# SparkFun_XBee3_Cat1_Smart_Modem_USB-C.net
KiCad netlist of a schematic drawn in EAGLE
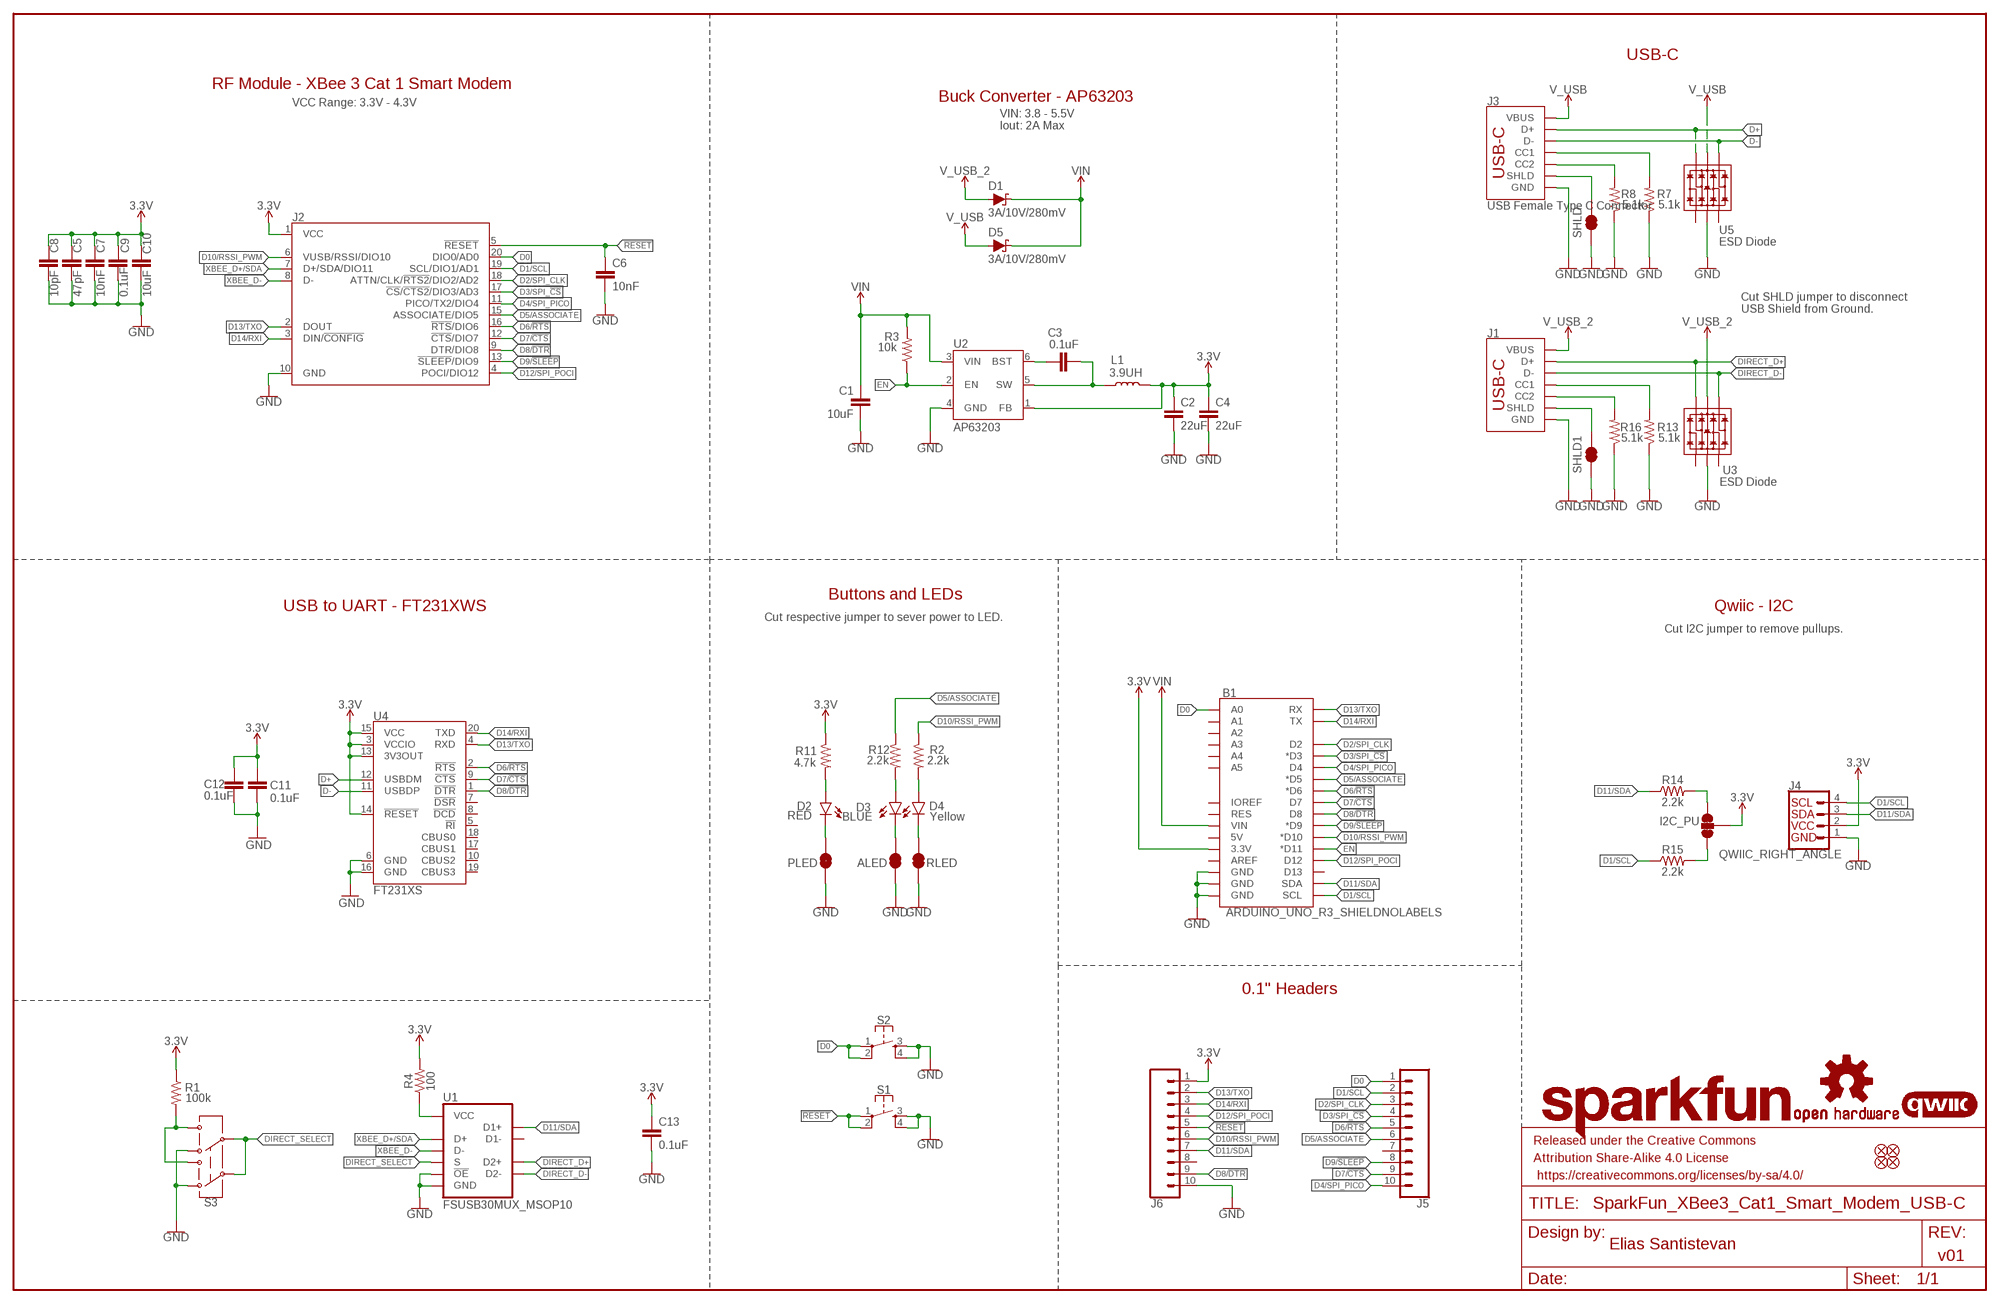
[diagram p0: schematic, sheet 1]

(export (version "E")
  (design (tool "Eeschema 10.0.6"))
  (components
    (comp (ref "ALED")
      (value "JUMPER-SMT_2_NC_TRACE_SILK")
      (footprint "eagle-import:SMT-JUMPER_2_NC_TRACE_SILK")
      (libsource (lib "eagle-import") (part "JUMPER-SMT_2_NC_TRACE_SILK"))
    )
    (comp (ref "B1")
      (value "ARDUINO_UNO_R3_SHIELDNOLABELS")
      (footprint "eagle-import:UNO_R3_SHIELD_NOLABELS")
      (libsource (lib "eagle-import") (part "ARDUINO_UNO_R3_SHIELDNOLABELS"))
    )
    (comp (ref "C1")
      (value "10uF")
      (footprint "eagle-import:1210")
      (libsource (lib "eagle-import") (part "10UF-1210-50V-20%"))
    )
    (comp (ref "C2")
      (value "22uF")
      (footprint "eagle-import:0603")
      (libsource (lib "eagle-import") (part "22UF-0603-6.3V-20%"))
    )
    (comp (ref "C3")
      (value "0.1uF")
      (footprint "eagle-import:0603")
      (libsource (lib "eagle-import") (part "0.1UF-0603-25V-5%"))
    )
    (comp (ref "C4")
      (value "22uF")
      (footprint "eagle-import:0603")
      (libsource (lib "eagle-import") (part "22UF-0603-6.3V-20%"))
    )
    (comp (ref "C5")
      (value "47pF")
      (footprint "eagle-import:0603")
      (libsource (lib "eagle-import") (part "47PF-0603-50V-5%"))
    )
    (comp (ref "C6")
      (value "10nF")
      (footprint "eagle-import:0603")
      (libsource (lib "eagle-import") (part "10NF-0603-50V-10%"))
    )
    (comp (ref "C7")
      (value "10nF")
      (footprint "eagle-import:0603")
      (libsource (lib "eagle-import") (part "10NF-0603-50V-10%"))
    )
    (comp (ref "C8")
      (value "10pF")
      (footprint "eagle-import:0603")
      (libsource (lib "eagle-import") (part "10PF-0603-50V-5%"))
    )
    (comp (ref "C9")
      (value "0.1uF")
      (footprint "eagle-import:0603")
      (libsource (lib "eagle-import") (part "0.1UF-0603-25V-(+80/-20%)"))
    )
    (comp (ref "C10")
      (value "10uF")
      (footprint "eagle-import:0603")
      (libsource (lib "eagle-import") (part "10UF-0603-6.3V-20%"))
    )
    (comp (ref "C11")
      (value "0.1uF")
      (footprint "eagle-import:0603")
      (libsource (lib "eagle-import") (part "0.1UF-0603-25V-(+80/-20%)"))
    )
    (comp (ref "C12")
      (value "0.1uF")
      (footprint "eagle-import:0603")
      (libsource (lib "eagle-import") (part "0.1UF-0603-25V-(+80/-20%)"))
    )
    (comp (ref "C13")
      (value "0.1uF")
      (footprint "eagle-import:0603")
      (libsource (lib "eagle-import") (part "0.1UF-0603-25V-(+80/-20%)"))
    )
    (comp (ref "D1")
      (value "3A/10V/280mV")
      (footprint "eagle-import:SOD-323")
      (libsource (lib "eagle-import") (part "DIODE-SCHOTTKY-BAT60A"))
    )
    (comp (ref "D2")
      (value "RED")
      (footprint "eagle-import:LED-0603")
      (libsource (lib "eagle-import") (part "LED-RED_0603-KB"))
    )
    (comp (ref "D3")
      (value "BLUE")
      (footprint "eagle-import:LED-0603")
      (libsource (lib "eagle-import") (part "LED-BLUE0603"))
    )
    (comp (ref "D4")
      (value "Yellow")
      (footprint "eagle-import:LED-0603")
      (libsource (lib "eagle-import") (part "LED-YELLOW0603"))
    )
    (comp (ref "D5")
      (value "3A/10V/280mV")
      (footprint "eagle-import:SOD-323")
      (libsource (lib "eagle-import") (part "DIODE-SCHOTTKY-BAT60A"))
    )
    (comp (ref "FD1")
      (value "FIDUCIAL1X2")
      (footprint "eagle-import:FIDUCIAL-1X2")
      (libsource (lib "eagle-import") (part "FIDUCIAL1X2"))
    )
    (comp (ref "FD2")
      (value "FIDUCIAL1X2")
      (footprint "eagle-import:FIDUCIAL-1X2")
      (libsource (lib "eagle-import") (part "FIDUCIAL1X2"))
    )
    (comp (ref "FD3")
      (value "FIDUCIAL1X2")
      (footprint "eagle-import:FIDUCIAL-1X2")
      (libsource (lib "eagle-import") (part "FIDUCIAL1X2"))
    )
    (comp (ref "FD4")
      (value "FIDUCIAL1X2")
      (footprint "eagle-import:FIDUCIAL-1X2")
      (libsource (lib "eagle-import") (part "FIDUCIAL1X2"))
    )
    (comp (ref "FRAME1")
      (value "FRAME-LEDGER")
      (footprint "eagle-import:CREATIVE_COMMONS")
      (libsource (lib "eagle-import") (part "FRAME-LEDGER"))
    )
    (comp (ref "I2C_PU")
      (value "JUMPER-SMT_3_2-NC_TRACE_SILK")
      (footprint "eagle-import:SMT-JUMPER_3_2-NC_TRACE_SILK")
      (libsource (lib "eagle-import") (part "JUMPER-SMT_3_2-NC_TRACE_SILK"))
    )
    (comp (ref "J1")
      (value "USB Female Type C Connector")
      (footprint "eagle-import:USB-C-16P-4LAYER-ISOLATED")
      (libsource (lib "eagle-import") (part "USB_C_4-LAYER-ISOLATED"))
    )
    (comp (ref "J2")
      (value "XBEE_UPDATEXBEE_SMD_SILK")
      (footprint "eagle-import:XBEE3-SMD_SILK")
      (libsource (lib "eagle-import") (part "XBEE_UPDATEXBEE_SMD_SILK"))
    )
    (comp (ref "J3")
      (value "USB Female Type C Connector")
      (footprint "eagle-import:USB-C-16P-4LAYER-ISOLATED")
      (libsource (lib "eagle-import") (part "USB_C_4-LAYER-ISOLATED"))
    )
    (comp (ref "J4")
      (value "QWIIC_RIGHT_ANGLE")
      (footprint "eagle-import:JST04_1MM_RA")
      (libsource (lib "eagle-import") (part "QWIIC_CONNECTORJS-1MM"))
    )
    (comp (ref "J5")
      (value "CONN_10NO_SILK_PTH_FEMALE")
      (footprint "eagle-import:1X10_NO_SILK")
      (libsource (lib "eagle-import") (part "CONN_10NO_SILK_PTH_FEMALE"))
    )
    (comp (ref "J6")
      (value "CONN_10NO_SILK_PTH_FEMALE")
      (footprint "eagle-import:1X10_NO_SILK")
      (libsource (lib "eagle-import") (part "CONN_10NO_SILK_PTH_FEMALE"))
    )
    (comp (ref "L1")
      (value "3.9UH")
      (footprint "eagle-import:INDUCTOR_3.9UH")
      (libsource (lib "eagle-import") (part "3.9UH"))
    )
    (comp (ref "LOGO1")
      (value "SFE_LOGO_NAME.1_INCH")
      (footprint "eagle-import:SFE_LOGO_NAME_.1")
      (libsource (lib "eagle-import") (part "SFE_LOGO_NAME.1_INCH"))
    )
    (comp (ref "LOGO2")
      (value "OSHW-LOGOS")
      (footprint "eagle-import:OSHW-LOGO-S")
      (libsource (lib "eagle-import") (part "OSHW-LOGOS"))
    )
    (comp (ref "LOGO3")
      (value "QWIIC_LOGO_3MM")
      (footprint "eagle-import:QWIIC_3MM")
      (libsource (lib "eagle-import") (part "QWIIC_LOGO_3MM"))
    )
    (comp (ref "PLED")
      (value "JUMPER-SMT_2_NC_TRACE_SILK")
      (footprint "eagle-import:SMT-JUMPER_2_NC_TRACE_SILK")
      (libsource (lib "eagle-import") (part "JUMPER-SMT_2_NC_TRACE_SILK"))
    )
    (comp (ref "R1")
      (value "100k")
      (footprint "eagle-import:0603")
      (libsource (lib "eagle-import") (part "100KOHM-0603-1/10W-1%"))
    )
    (comp (ref "R2")
      (value "2.2k")
      (footprint "eagle-import:0603")
      (libsource (lib "eagle-import") (part "2.2KOHM-0603-1/10W-1%"))
    )
    (comp (ref "R3")
      (value "10k")
      (footprint "eagle-import:0603")
      (libsource (lib "eagle-import") (part "10KOHM-0603-1/10W-1%"))
    )
    (comp (ref "R4")
      (value "100")
      (footprint "eagle-import:0603")
      (libsource (lib "eagle-import") (part "100OHM-0603-1/10W-1%"))
    )
    (comp (ref "R7")
      (value "5.1k")
      (footprint "eagle-import:0603")
      (libsource (lib "eagle-import") (part "5.1KOHM5.1KOHM-0603-1/10W-1%"))
    )
    (comp (ref "R8")
      (value "5.1k")
      (footprint "eagle-import:0603")
      (libsource (lib "eagle-import") (part "5.1KOHM5.1KOHM-0603-1/10W-1%"))
    )
    (comp (ref "R11")
      (value "4.7k")
      (footprint "eagle-import:0603")
      (libsource (lib "eagle-import") (part "4.7KOHM-0603-1/10W-1%"))
    )
    (comp (ref "R12")
      (value "2.2k")
      (footprint "eagle-import:0603")
      (libsource (lib "eagle-import") (part "2.2KOHM-0603-1/10W-1%"))
    )
    (comp (ref "R13")
      (value "5.1k")
      (footprint "eagle-import:0603")
      (libsource (lib "eagle-import") (part "5.1KOHM5.1KOHM-0603-1/10W-1%"))
    )
    (comp (ref "R14")
      (value "2.2k")
      (footprint "eagle-import:0603")
      (libsource (lib "eagle-import") (part "2.2KOHM-0603-1/10W-1%"))
    )
    (comp (ref "R15")
      (value "2.2k")
      (footprint "eagle-import:0603")
      (libsource (lib "eagle-import") (part "2.2KOHM-0603-1/10W-1%"))
    )
    (comp (ref "R16")
      (value "5.1k")
      (footprint "eagle-import:0603")
      (libsource (lib "eagle-import") (part "5.1KOHM5.1KOHM-0603-1/10W-1%"))
    )
    (comp (ref "RLED")
      (value "JUMPER-SMT_2_NC_TRACE_SILK")
      (footprint "eagle-import:SMT-JUMPER_2_NC_TRACE_SILK")
      (libsource (lib "eagle-import") (part "JUMPER-SMT_2_NC_TRACE_SILK"))
    )
    (comp (ref "S1")
      (value "MOMENTARY-SWITCH-SPST-2-SMD-5.2MM-TALL")
      (footprint "eagle-import:TACTILE_SWITCH_SMD_5.2MM")
      (libsource (lib "eagle-import") (part "MOMENTARY-SWITCH-SPST-2-SMD-5.2MM-TALL"))
    )
    (comp (ref "S2")
      (value "MOMENTARY-SWITCH-SPST-2-SMD-5.2MM-TALL")
      (footprint "eagle-import:TACTILE_SWITCH_SMD_5.2MM")
      (libsource (lib "eagle-import") (part "MOMENTARY-SWITCH-SPST-2-SMD-5.2MM-TALL"))
    )
    (comp (ref "S3")
      (value "SWITCH-DPDT-SMD-AYZ0202")
      (footprint "eagle-import:SWITCH_DPDT_SMD_AYZ0202")
      (libsource (lib "eagle-import") (part "SWITCH-DPDT-SMD-AYZ0202"))
    )
    (comp (ref "SHLD")
      (value "JUMPER-SMT_2_NC_TRACE_SILK")
      (footprint "eagle-import:SMT-JUMPER_2_NC_TRACE_SILK")
      (libsource (lib "eagle-import") (part "JUMPER-SMT_2_NC_TRACE_SILK"))
    )
    (comp (ref "SHLD1")
      (value "JUMPER-SMT_2_NC_TRACE_SILK")
      (footprint "eagle-import:SMT-JUMPER_2_NC_TRACE_SILK")
      (libsource (lib "eagle-import") (part "JUMPER-SMT_2_NC_TRACE_SILK"))
    )
    (comp (ref "U1")
      (value "FSUSB30MUX_MSOP10")
      (footprint "eagle-import:MSOP10")
      (libsource (lib "eagle-import") (part "FSUSB30MUX_MSOP10"))
    )
    (comp (ref "U2")
      (value "AP63203")
      (footprint "eagle-import:SOT23-6")
      (libsource (lib "eagle-import") (part "AP63203"))
    )
    (comp (ref "U3")
      (value "ESD Diode")
      (footprint "eagle-import:SOT-23-6")
      (libsource (lib "eagle-import") (part "TVS_DIODE_ARRAY_DT1042-04SO-7"))
    )
    (comp (ref "U4")
      (value "FT231XS")
      (footprint "eagle-import:SSOP20_L")
      (libsource (lib "eagle-import") (part "FT231XS"))
    )
    (comp (ref "U5")
      (value "ESD Diode")
      (footprint "eagle-import:SOT-23-6")
      (libsource (lib "eagle-import") (part "TVS_DIODE_ARRAY_DT1042-04SO-7"))
    )
  )
  (nets
    (net (code "1") (name "/D3{slash}SPI_~{CS}") (class "Default")
      (node (ref "B1") (pin "D3") (pinfunction "*D3_D3") (pintype "bidirectional"))
      (node (ref "J2") (pin "17") (pinfunction "~{CS}/~{CTS2}/DIO3/AD3_17") (pintype "bidirectional"))
      (node (ref "J5") (pin "4") (pinfunction "4_4") (pintype "passive"))
    )
    (net (code "2") (name "/D6{slash}~{RTS}") (class "Default")
      (node (ref "B1") (pin "D6") (pinfunction "*D6_D6") (pintype "bidirectional"))
      (node (ref "J2") (pin "16") (pinfunction "~{RTS}/DIO6_16") (pintype "input"))
      (node (ref "J5") (pin "5") (pinfunction "5_5") (pintype "passive"))
      (node (ref "U4") (pin "2") (pinfunction "~{RTS}_2") (pintype "bidirectional"))
    )
    (net (code "3") (name "/D7{slash}~{CTS}") (class "Default")
      (node (ref "B1") (pin "D7") (pinfunction "D7_D7") (pintype "bidirectional"))
      (node (ref "J2") (pin "12") (pinfunction "~{CTS}/DIO7_12") (pintype "output"))
      (node (ref "J5") (pin "9") (pinfunction "9_9") (pintype "passive"))
      (node (ref "U4") (pin "9") (pinfunction "~{CTS}_9") (pintype "bidirectional"))
    )
    (net (code "4") (name "/D8{slash}~{DTR}") (class "Default")
      (node (ref "B1") (pin "D8") (pinfunction "D8_D8") (pintype "bidirectional"))
      (node (ref "J2") (pin "9") (pinfunction "DTR/DIO8_9") (pintype "bidirectional"))
      (node (ref "J6") (pin "9") (pinfunction "9_9") (pintype "passive"))
      (node (ref "U4") (pin "1") (pinfunction "~{DTR}_1") (pintype "bidirectional"))
    )
    (net (code "5") (name "/D9{slash}~{SLEEP}") (class "Default")
      (node (ref "B1") (pin "D9") (pinfunction "*D9_D9") (pintype "bidirectional"))
      (node (ref "J2") (pin "13") (pinfunction "~{SLEEP}/DIO9_13") (pintype "bidirectional"))
      (node (ref "J5") (pin "8") (pinfunction "8_8") (pintype "passive"))
    )
    (net (code "6") (name "/~{RESET}") (class "Default")
      (node (ref "C6") (pin "1") (pinfunction "1_1") (pintype "passive"))
      (node (ref "J2") (pin "5") (pinfunction "~{RESET}_5") (pintype "input"))
      (node (ref "J6") (pin "5") (pinfunction "5_5") (pintype "passive"))
      (node (ref "S1") (pin "1") (pinfunction "1_1") (pintype "passive"))
      (node (ref "S1") (pin "2") (pinfunction "2_2") (pintype "passive"))
    )
    (net (code "7") (name "3.3V") (class "Default")
      (node (ref "B1") (pin "3.3V") (pinfunction "3.3V_3.3V") (pintype "bidirectional"))
      (node (ref "C10") (pin "1") (pinfunction "1_1") (pintype "passive"))
      (node (ref "C11") (pin "1") (pinfunction "1_1") (pintype "passive"))
      (node (ref "C12") (pin "1") (pinfunction "1_1") (pintype "passive"))
      (node (ref "C13") (pin "1") (pinfunction "1_1") (pintype "passive"))
      (node (ref "C2") (pin "1") (pinfunction "1_1") (pintype "passive"))
      (node (ref "C4") (pin "1") (pinfunction "1_1") (pintype "passive"))
      (node (ref "C5") (pin "1") (pinfunction "1_1") (pintype "passive"))
      (node (ref "C7") (pin "1") (pinfunction "1_1") (pintype "passive"))
      (node (ref "C8") (pin "1") (pinfunction "1_1") (pintype "passive"))
      (node (ref "C9") (pin "1") (pinfunction "1_1") (pintype "passive"))
      (node (ref "I2C_PU") (pin "2") (pinfunction "2_2") (pintype "passive"))
      (node (ref "J2") (pin "1") (pinfunction "VCC_1") (pintype "power_in"))
      (node (ref "J4") (pin "2") (pinfunction "2_2") (pintype "power_in"))
      (node (ref "J6") (pin "1") (pinfunction "1_1") (pintype "passive"))
      (node (ref "L1") (pin "P$2") (pinfunction "2_P$2") (pintype "passive"))
      (node (ref "R1") (pin "1") (pinfunction "1_1") (pintype "passive"))
      (node (ref "R11") (pin "1") (pinfunction "1_1") (pintype "passive"))
      (node (ref "R4") (pin "2") (pinfunction "2_2") (pintype "passive"))
      (node (ref "U2") (pin "1") (pinfunction "FB_1") (pintype "bidirectional"))
      (node (ref "U4") (pin "13") (pinfunction "3V3OUT_13") (pintype "bidirectional"))
      (node (ref "U4") (pin "14") (pinfunction "~{RESET}_14") (pintype "bidirectional"))
      (node (ref "U4") (pin "15") (pinfunction "VCC_15") (pintype "bidirectional"))
      (node (ref "U4") (pin "3") (pinfunction "VCCIO_3") (pintype "bidirectional"))
    )
    (net (code "8") (name "D+") (class "Default")
      (node (ref "J3") (pin "A6") (pinfunction "D+_A6") (pintype "bidirectional"))
      (node (ref "J3") (pin "B6") (pinfunction "D+_B6") (pintype "bidirectional"))
      (node (ref "U4") (pin "12") (pinfunction "USBDM_12") (pintype "bidirectional"))
      (node (ref "U5") (pin "6") (pinfunction "IO4_6") (pintype "bidirectional"))
    )
    (net (code "9") (name "D-") (class "Default")
      (node (ref "J3") (pin "A7") (pinfunction "D-_A7") (pintype "bidirectional"))
      (node (ref "J3") (pin "B7") (pinfunction "D-_B7") (pintype "bidirectional"))
      (node (ref "U4") (pin "11") (pinfunction "USBDP_11") (pintype "bidirectional"))
      (node (ref "U5") (pin "4") (pinfunction "IO3_4") (pintype "bidirectional"))
    )
    (net (code "10") (name "D0") (class "Default")
      (node (ref "B1") (pin "A0") (pinfunction "A0_A0") (pintype "bidirectional"))
      (node (ref "J2") (pin "20") (pinfunction "DIO0/AD0_20") (pintype "bidirectional"))
      (node (ref "J5") (pin "1") (pinfunction "1_1") (pintype "passive"))
      (node (ref "S2") (pin "1") (pinfunction "1_1") (pintype "passive"))
      (node (ref "S2") (pin "2") (pinfunction "2_2") (pintype "passive"))
    )
    (net (code "11") (name "D1{slash}SCL") (class "Default")
      (node (ref "B1") (pin "SCL") (pinfunction "SCL_SCL") (pintype "bidirectional"))
      (node (ref "J2") (pin "19") (pinfunction "SCL/DIO1/AD1_19") (pintype "bidirectional"))
      (node (ref "J4") (pin "4") (pinfunction "4_4") (pintype "passive"))
      (node (ref "J5") (pin "2") (pinfunction "2_2") (pintype "passive"))
      (node (ref "R15") (pin "1") (pinfunction "1_1") (pintype "passive"))
    )
    (net (code "12") (name "D2{slash}SPI_CLK") (class "Default")
      (node (ref "B1") (pin "D2") (pinfunction "D2_D2") (pintype "bidirectional"))
      (node (ref "J2") (pin "18") (pinfunction "ATTN/CLK/~{RTS2}/DIO2/AD2_18") (pintype "bidirectional"))
      (node (ref "J5") (pin "3") (pinfunction "3_3") (pintype "passive"))
    )
    (net (code "13") (name "D4{slash}SPI_PICO") (class "Default")
      (node (ref "B1") (pin "D4") (pinfunction "D4_D4") (pintype "bidirectional"))
      (node (ref "J2") (pin "11") (pinfunction "PICO/TX2/DIO4_11") (pintype "bidirectional"))
      (node (ref "J5") (pin "10") (pinfunction "10_10") (pintype "passive"))
    )
    (net (code "14") (name "D5{slash}ASSOCIATE") (class "Default")
      (node (ref "B1") (pin "D5") (pinfunction "*D5_D5") (pintype "bidirectional"))
      (node (ref "J2") (pin "15") (pinfunction "ASSOCIATE/DIO5_15") (pintype "bidirectional"))
      (node (ref "J5") (pin "6") (pinfunction "6_6") (pintype "passive"))
      (node (ref "R12") (pin "1") (pinfunction "1_1") (pintype "passive"))
    )
    (net (code "15") (name "D10{slash}RSSI_PWM") (class "Default")
      (node (ref "B1") (pin "D10") (pinfunction "*D10_D10") (pintype "bidirectional"))
      (node (ref "J2") (pin "6") (pinfunction "VUSB/RSSI/DIO10_6") (pintype "bidirectional"))
      (node (ref "J6") (pin "6") (pinfunction "6_6") (pintype "passive"))
      (node (ref "R2") (pin "1") (pinfunction "1_1") (pintype "passive"))
    )
    (net (code "16") (name "D11{slash}SDA") (class "Default")
      (node (ref "B1") (pin "SDA") (pinfunction "SDA_SDA") (pintype "bidirectional"))
      (node (ref "J4") (pin "3") (pinfunction "3_3") (pintype "passive"))
      (node (ref "J6") (pin "7") (pinfunction "7_7") (pintype "passive"))
      (node (ref "R14") (pin "1") (pinfunction "1_1") (pintype "passive"))
      (node (ref "U1") (pin "2") (pinfunction "D1+_2") (pintype "bidirectional"))
    )
    (net (code "17") (name "D12{slash}SPI_POCI") (class "Default")
      (node (ref "B1") (pin "D12") (pinfunction "D12_D12") (pintype "bidirectional"))
      (node (ref "J2") (pin "4") (pinfunction "POCI/DIO12_4") (pintype "bidirectional"))
      (node (ref "J6") (pin "4") (pinfunction "4_4") (pintype "passive"))
    )
    (net (code "18") (name "D13{slash}TXO") (class "Default")
      (node (ref "B1") (pin "RX") (pinfunction "RX_RX") (pintype "bidirectional"))
      (node (ref "J2") (pin "2") (pinfunction "DOUT_2") (pintype "output"))
      (node (ref "J6") (pin "2") (pinfunction "2_2") (pintype "passive"))
      (node (ref "U4") (pin "4") (pinfunction "RXD_4") (pintype "bidirectional"))
    )
    (net (code "19") (name "D14{slash}RXI") (class "Default")
      (node (ref "B1") (pin "TX") (pinfunction "TX_TX") (pintype "bidirectional"))
      (node (ref "J2") (pin "3") (pinfunction "DIN/~{CONFIG}_3") (pintype "input"))
      (node (ref "J6") (pin "3") (pinfunction "3_3") (pintype "passive"))
      (node (ref "U4") (pin "20") (pinfunction "TXD_20") (pintype "bidirectional"))
    )
    (net (code "20") (name "DIRECT_D+") (class "Default")
      (node (ref "J1") (pin "A6") (pinfunction "D+_A6") (pintype "bidirectional"))
      (node (ref "J1") (pin "B6") (pinfunction "D+_B6") (pintype "bidirectional"))
      (node (ref "U1") (pin "3") (pinfunction "D2+_3") (pintype "bidirectional"))
      (node (ref "U3") (pin "6") (pinfunction "IO4_6") (pintype "bidirectional"))
    )
    (net (code "21") (name "DIRECT_D-") (class "Default")
      (node (ref "J1") (pin "A7") (pinfunction "D-_A7") (pintype "bidirectional"))
      (node (ref "J1") (pin "B7") (pinfunction "D-_B7") (pintype "bidirectional"))
      (node (ref "U1") (pin "7") (pinfunction "D2-_7") (pintype "bidirectional"))
      (node (ref "U3") (pin "4") (pinfunction "IO3_4") (pintype "bidirectional"))
    )
    (net (code "22") (name "DIRECT_SELECT") (class "Default")
      (node (ref "S3") (pin "2") (pinfunction "2_2") (pintype "bidirectional"))
      (node (ref "S3") (pin "5") (pinfunction "5_5") (pintype "bidirectional"))
      (node (ref "U1") (pin "1") (pinfunction "S_1") (pintype "bidirectional"))
    )
    (net (code "23") (name "EN") (class "Default")
      (node (ref "B1") (pin "D11") (pinfunction "*D11_D11") (pintype "bidirectional"))
      (node (ref "R3") (pin "1") (pinfunction "1_1") (pintype "passive"))
      (node (ref "U2") (pin "2") (pinfunction "EN_2") (pintype "bidirectional"))
    )
    (net (code "24") (name "GND") (class "Default")
      (node (ref "ALED") (pin "1") (pinfunction "1_1") (pintype "passive"))
      (node (ref "B1") (pin "GND@0") (pinfunction "GND_GND@0") (pintype "bidirectional"))
      (node (ref "B1") (pin "GND@1") (pinfunction "GND_GND@1") (pintype "bidirectional"))
      (node (ref "B1") (pin "GND@2") (pinfunction "GND_GND@2") (pintype "bidirectional"))
      (node (ref "C1") (pin "2") (pinfunction "2_2") (pintype "passive"))
      (node (ref "C10") (pin "2") (pinfunction "2_2") (pintype "passive"))
      (node (ref "C11") (pin "2") (pinfunction "2_2") (pintype "passive"))
      (node (ref "C12") (pin "2") (pinfunction "2_2") (pintype "passive"))
      (node (ref "C13") (pin "2") (pinfunction "2_2") (pintype "passive"))
      (node (ref "C2") (pin "2") (pinfunction "2_2") (pintype "passive"))
      (node (ref "C4") (pin "2") (pinfunction "2_2") (pintype "passive"))
      (node (ref "C5") (pin "2") (pinfunction "2_2") (pintype "passive"))
      (node (ref "C6") (pin "2") (pinfunction "2_2") (pintype "passive"))
      (node (ref "C7") (pin "2") (pinfunction "2_2") (pintype "passive"))
      (node (ref "C8") (pin "2") (pinfunction "2_2") (pintype "passive"))
      (node (ref "C9") (pin "2") (pinfunction "2_2") (pintype "passive"))
      (node (ref "J1") (pin "GND") (pinfunction "GND_GND") (pintype "bidirectional"))
      (node (ref "J1") (pin "GND2") (pinfunction "GND_GND2") (pintype "bidirectional"))
      (node (ref "J2") (pin "10") (pinfunction "GND_10") (pintype "power_in"))
      (node (ref "J3") (pin "GND") (pinfunction "GND_GND") (pintype "bidirectional"))
      (node (ref "J3") (pin "GND2") (pinfunction "GND_GND2") (pintype "bidirectional"))
      (node (ref "J4") (pin "1") (pinfunction "1_1") (pintype "power_in"))
      (node (ref "J6") (pin "10") (pinfunction "10_10") (pintype "passive"))
      (node (ref "PLED") (pin "1") (pinfunction "1_1") (pintype "passive"))
      (node (ref "R13") (pin "1") (pinfunction "1_1") (pintype "passive"))
      (node (ref "R16") (pin "1") (pinfunction "1_1") (pintype "passive"))
      (node (ref "R7") (pin "1") (pinfunction "1_1") (pintype "passive"))
      (node (ref "R8") (pin "1") (pinfunction "1_1") (pintype "passive"))
      (node (ref "RLED") (pin "1") (pinfunction "1_1") (pintype "passive"))
      (node (ref "S1") (pin "3") (pinfunction "3_3") (pintype "passive"))
      (node (ref "S1") (pin "4") (pinfunction "4_4") (pintype "passive"))
      (node (ref "S2") (pin "3") (pinfunction "3_3") (pintype "passive"))
      (node (ref "S2") (pin "4") (pinfunction "4_4") (pintype "passive"))
      (node (ref "S3") (pin "3") (pinfunction "3_3") (pintype "bidirectional"))
      (node (ref "S3") (pin "6") (pinfunction "6_6") (pintype "bidirectional"))
      (node (ref "SHLD") (pin "1") (pinfunction "1_1") (pintype "passive"))
      (node (ref "SHLD1") (pin "1") (pinfunction "1_1") (pintype "passive"))
      (node (ref "U1") (pin "5") (pinfunction "GND_5") (pintype "bidirectional"))
      (node (ref "U1") (pin "9") (pinfunction "~{OE}_9") (pintype "bidirectional"))
      (node (ref "U2") (pin "4") (pinfunction "GND_4") (pintype "bidirectional"))
      (node (ref "U3") (pin "2") (pinfunction "VSS_2") (pintype "bidirectional"))
      (node (ref "U4") (pin "16") (pinfunction "GND_16") (pintype "bidirectional"))
      (node (ref "U4") (pin "6") (pinfunction "GND_6") (pintype "bidirectional"))
      (node (ref "U5") (pin "2") (pinfunction "VSS_2") (pintype "bidirectional"))
    )
    (net (code "25") (name "Net-(ALED-Pad2)") (class "Default")
      (node (ref "ALED") (pin "2") (pinfunction "2_2") (pintype "passive"))
      (node (ref "D3") (pin "C") (pinfunction "C_C") (pintype "passive"))
    )
    (net (code "26") (name "Net-(D2-PadA)") (class "Default")
      (node (ref "D2") (pin "A") (pinfunction "A_A") (pintype "passive"))
      (node (ref "R11") (pin "2") (pinfunction "2_2") (pintype "passive"))
    )
    (net (code "27") (name "Net-(D2-PadC)") (class "Default")
      (node (ref "D2") (pin "C") (pinfunction "C_C") (pintype "passive"))
      (node (ref "PLED") (pin "2") (pinfunction "2_2") (pintype "passive"))
    )
    (net (code "28") (name "Net-(D3-PadA)") (class "Default")
      (node (ref "D3") (pin "A") (pinfunction "A_A") (pintype "passive"))
      (node (ref "R12") (pin "2") (pinfunction "2_2") (pintype "passive"))
    )
    (net (code "29") (name "Net-(D4-PadA)") (class "Default")
      (node (ref "D4") (pin "A") (pinfunction "A_A") (pintype "passive"))
      (node (ref "R2") (pin "2") (pinfunction "2_2") (pintype "passive"))
    )
    (net (code "30") (name "Net-(D4-PadC)") (class "Default")
      (node (ref "D4") (pin "C") (pinfunction "C_C") (pintype "passive"))
      (node (ref "RLED") (pin "2") (pinfunction "2_2") (pintype "passive"))
    )
    (net (code "31") (name "Net-(I2C_PU-Pad1)") (class "Default")
      (node (ref "I2C_PU") (pin "1") (pinfunction "1_1") (pintype "passive"))
      (node (ref "R15") (pin "2") (pinfunction "2_2") (pintype "passive"))
    )
    (net (code "32") (name "Net-(I2C_PU-Pad3)") (class "Default")
      (node (ref "I2C_PU") (pin "3") (pinfunction "3_3") (pintype "passive"))
      (node (ref "R14") (pin "2") (pinfunction "2_2") (pintype "passive"))
    )
    (net (code "33") (name "Net-(J1-CC1)") (class "Default")
      (node (ref "J1") (pin "A5") (pinfunction "CC1_A5") (pintype "bidirectional"))
      (node (ref "R13") (pin "2") (pinfunction "2_2") (pintype "passive"))
    )
    (net (code "34") (name "Net-(J1-CC2)") (class "Default")
      (node (ref "J1") (pin "B5") (pinfunction "CC2_B5") (pintype "bidirectional"))
      (node (ref "R16") (pin "2") (pinfunction "2_2") (pintype "passive"))
    )
    (net (code "35") (name "Net-(J1-SHLD-PadSHLD1)") (class "Default")
      (node (ref "J1") (pin "SHLD1") (pinfunction "SHLD_SHLD1") (pintype "bidirectional"))
      (node (ref "J1") (pin "SHLD2") (pinfunction "SHLD_SHLD2") (pintype "bidirectional"))
      (node (ref "J1") (pin "SHLD3") (pinfunction "SHLD_SHLD3") (pintype "bidirectional"))
      (node (ref "J1") (pin "SHLD4") (pinfunction "SHLD_SHLD4") (pintype "bidirectional"))
      (node (ref "J1") (pin "SHLD5") (pinfunction "SHLD_SHLD5") (pintype "bidirectional"))
      (node (ref "J1") (pin "SHLD6") (pinfunction "SHLD_SHLD6") (pintype "bidirectional"))
      (node (ref "J1") (pin "SHLD7") (pinfunction "SHLD_SHLD7") (pintype "bidirectional"))
      (node (ref "J1") (pin "SHLD8") (pinfunction "SHLD_SHLD8") (pintype "bidirectional"))
      (node (ref "SHLD1") (pin "2") (pinfunction "2_2") (pintype "passive"))
    )
    (net (code "36") (name "Net-(J3-CC1)") (class "Default")
      (node (ref "J3") (pin "A5") (pinfunction "CC1_A5") (pintype "bidirectional"))
      (node (ref "R7") (pin "2") (pinfunction "2_2") (pintype "passive"))
    )
    (net (code "37") (name "Net-(J3-CC2)") (class "Default")
      (node (ref "J3") (pin "B5") (pinfunction "CC2_B5") (pintype "bidirectional"))
      (node (ref "R8") (pin "2") (pinfunction "2_2") (pintype "passive"))
    )
    (net (code "38") (name "Net-(J3-SHLD-PadSHLD1)") (class "Default")
      (node (ref "J3") (pin "SHLD1") (pinfunction "SHLD_SHLD1") (pintype "bidirectional"))
      (node (ref "J3") (pin "SHLD2") (pinfunction "SHLD_SHLD2") (pintype "bidirectional"))
      (node (ref "J3") (pin "SHLD3") (pinfunction "SHLD_SHLD3") (pintype "bidirectional"))
      (node (ref "J3") (pin "SHLD4") (pinfunction "SHLD_SHLD4") (pintype "bidirectional"))
      (node (ref "J3") (pin "SHLD5") (pinfunction "SHLD_SHLD5") (pintype "bidirectional"))
      (node (ref "J3") (pin "SHLD6") (pinfunction "SHLD_SHLD6") (pintype "bidirectional"))
      (node (ref "J3") (pin "SHLD7") (pinfunction "SHLD_SHLD7") (pintype "bidirectional"))
      (node (ref "J3") (pin "SHLD8") (pinfunction "SHLD_SHLD8") (pintype "bidirectional"))
      (node (ref "SHLD") (pin "2") (pinfunction "2_2") (pintype "passive"))
    )
    (net (code "39") (name "Net-(L1-1)") (class "Default")
      (node (ref "C3") (pin "2") (pinfunction "2_2") (pintype "passive"))
      (node (ref "L1") (pin "P$1") (pinfunction "1_P$1") (pintype "passive"))
      (node (ref "U2") (pin "5") (pinfunction "SW_5") (pintype "bidirectional"))
    )
    (net (code "40") (name "Net-(R1-Pad2)") (class "Default")
      (node (ref "R1") (pin "2") (pinfunction "2_2") (pintype "passive"))
      (node (ref "S3") (pin "1") (pinfunction "1_1") (pintype "bidirectional"))
      (node (ref "S3") (pin "4") (pinfunction "4_4") (pintype "bidirectional"))
    )
    (net (code "41") (name "Net-(U1-VCC)") (class "Default")
      (node (ref "R4") (pin "1") (pinfunction "1_1") (pintype "passive"))
      (node (ref "U1") (pin "10") (pinfunction "VCC_10") (pintype "bidirectional"))
    )
    (net (code "42") (name "Net-(U2-BST)") (class "Default")
      (node (ref "C3") (pin "1") (pinfunction "1_1") (pintype "passive"))
      (node (ref "U2") (pin "6") (pinfunction "BST_6") (pintype "bidirectional"))
    )
    (net (code "43") (name "VIN") (class "Default")
      (node (ref "B1") (pin "VIN") (pinfunction "VIN_VIN") (pintype "bidirectional"))
      (node (ref "C1") (pin "1") (pinfunction "1_1") (pintype "passive"))
      (node (ref "D1") (pin "C") (pinfunction "C_C") (pintype "passive"))
      (node (ref "D5") (pin "C") (pinfunction "C_C") (pintype "passive"))
      (node (ref "R3") (pin "2") (pinfunction "2_2") (pintype "passive"))
      (node (ref "U2") (pin "3") (pinfunction "VIN_3") (pintype "bidirectional"))
    )
    (net (code "44") (name "V_USB") (class "Default")
      (node (ref "D5") (pin "A") (pinfunction "A_A") (pintype "passive"))
      (node (ref "J3") (pin "VBUS1") (pinfunction "VBUS_VBUS1") (pintype "bidirectional"))
      (node (ref "J3") (pin "VBUS2") (pinfunction "VBUS_VBUS2") (pintype "bidirectional"))
      (node (ref "U5") (pin "5") (pinfunction "VCC_5") (pintype "bidirectional"))
    )
    (net (code "45") (name "V_USB_2") (class "Default")
      (node (ref "D1") (pin "A") (pinfunction "A_A") (pintype "passive"))
      (node (ref "J1") (pin "VBUS1") (pinfunction "VBUS_VBUS1") (pintype "bidirectional"))
      (node (ref "J1") (pin "VBUS2") (pinfunction "VBUS_VBUS2") (pintype "bidirectional"))
      (node (ref "U3") (pin "5") (pinfunction "VCC_5") (pintype "bidirectional"))
    )
    (net (code "46") (name "XBEE_D+{slash}SDA") (class "Default")
      (node (ref "J2") (pin "7") (pinfunction "D+/SDA/DIO11_7") (pintype "bidirectional"))
      (node (ref "U1") (pin "4") (pinfunction "D+_4") (pintype "bidirectional"))
    )
    (net (code "47") (name "XBEE_D-") (class "Default")
      (node (ref "J2") (pin "8") (pinfunction "D-_8") (pintype "bidirectional"))
      (node (ref "U1") (pin "6") (pinfunction "D-_6") (pintype "bidirectional"))
    )
    (net (code "48") (name "unconnected-(B1-Pad5V)") (class "Default")
      (node (ref "B1") (pin "5V") (pinfunction "5V_5V") (pintype "bidirectional"))
    )
    (net (code "49") (name "unconnected-(B1-PadA1)") (class "Default")
      (node (ref "B1") (pin "A1") (pinfunction "A1_A1") (pintype "bidirectional"))
    )
    (net (code "50") (name "unconnected-(B1-PadA2)") (class "Default")
      (node (ref "B1") (pin "A2") (pinfunction "A2_A2") (pintype "bidirectional"))
    )
    (net (code "51") (name "unconnected-(B1-PadA3)") (class "Default")
      (node (ref "B1") (pin "A3") (pinfunction "A3_A3") (pintype "bidirectional"))
    )
    (net (code "52") (name "unconnected-(B1-PadA4)") (class "Default")
      (node (ref "B1") (pin "A4") (pinfunction "A4_A4") (pintype "bidirectional"))
    )
    (net (code "53") (name "unconnected-(B1-PadA5)") (class "Default")
      (node (ref "B1") (pin "A5") (pinfunction "A5_A5") (pintype "bidirectional"))
    )
    (net (code "54") (name "unconnected-(B1-PadAREF)") (class "Default")
      (node (ref "B1") (pin "AREF") (pinfunction "AREF_AREF") (pintype "bidirectional"))
    )
    (net (code "55") (name "unconnected-(B1-PadD13)") (class "Default")
      (node (ref "B1") (pin "D13") (pinfunction "D13_D13") (pintype "bidirectional"))
    )
    (net (code "56") (name "unconnected-(B1-PadIOREF)") (class "Default")
      (node (ref "B1") (pin "IOREF") (pinfunction "IOREF_IOREF") (pintype "bidirectional"))
    )
    (net (code "57") (name "unconnected-(B1-PadRES)") (class "Default")
      (node (ref "B1") (pin "RES") (pinfunction "RES_RES") (pintype "bidirectional"))
    )
    (net (code "58") (name "unconnected-(J5-Pad7)") (class "Default")
      (node (ref "J5") (pin "7") (pinfunction "7_7") (pintype "passive"))
    )
    (net (code "59") (name "unconnected-(J6-Pad8)") (class "Default")
      (node (ref "J6") (pin "8") (pinfunction "8_8") (pintype "passive"))
    )
    (net (code "60") (name "unconnected-(U1-D1--Pad8)") (class "Default")
      (node (ref "U1") (pin "8") (pinfunction "D1-_8") (pintype "bidirectional"))
    )
    (net (code "61") (name "unconnected-(U3-IO1-Pad1)") (class "Default")
      (node (ref "U3") (pin "1") (pinfunction "IO1_1") (pintype "bidirectional"))
    )
    (net (code "62") (name "unconnected-(U3-IO2-Pad3)") (class "Default")
      (node (ref "U3") (pin "3") (pinfunction "IO2_3") (pintype "bidirectional"))
    )
    (net (code "63") (name "unconnected-(U4-CBUS0-Pad18)") (class "Default")
      (node (ref "U4") (pin "18") (pinfunction "CBUS0_18") (pintype "bidirectional"))
    )
    (net (code "64") (name "unconnected-(U4-CBUS1-Pad17)") (class "Default")
      (node (ref "U4") (pin "17") (pinfunction "CBUS1_17") (pintype "bidirectional"))
    )
    (net (code "65") (name "unconnected-(U4-CBUS2-Pad10)") (class "Default")
      (node (ref "U4") (pin "10") (pinfunction "CBUS2_10") (pintype "bidirectional"))
    )
    (net (code "66") (name "unconnected-(U4-CBUS3-Pad19)") (class "Default")
      (node (ref "U4") (pin "19") (pinfunction "CBUS3_19") (pintype "bidirectional"))
    )
    (net (code "67") (name "unconnected-(U4-~{DCD}-Pad8)") (class "Default")
      (node (ref "U4") (pin "8") (pinfunction "~{DCD}_8") (pintype "bidirectional"))
    )
    (net (code "68") (name "unconnected-(U4-~{DSR}-Pad7)") (class "Default")
      (node (ref "U4") (pin "7") (pinfunction "~{DSR}_7") (pintype "bidirectional"))
    )
    (net (code "69") (name "unconnected-(U4-~{RI}-Pad5)") (class "Default")
      (node (ref "U4") (pin "5") (pinfunction "~{RI}_5") (pintype "bidirectional"))
    )
    (net (code "70") (name "unconnected-(U5-IO1-Pad1)") (class "Default")
      (node (ref "U5") (pin "1") (pinfunction "IO1_1") (pintype "bidirectional"))
    )
    (net (code "71") (name "unconnected-(U5-IO2-Pad3)") (class "Default")
      (node (ref "U5") (pin "3") (pinfunction "IO2_3") (pintype "bidirectional"))
    )
  )
)
